# SparkFun_Micro_Bit_Moto_Bit.net
KiCad netlist of a schematic drawn in EAGLE
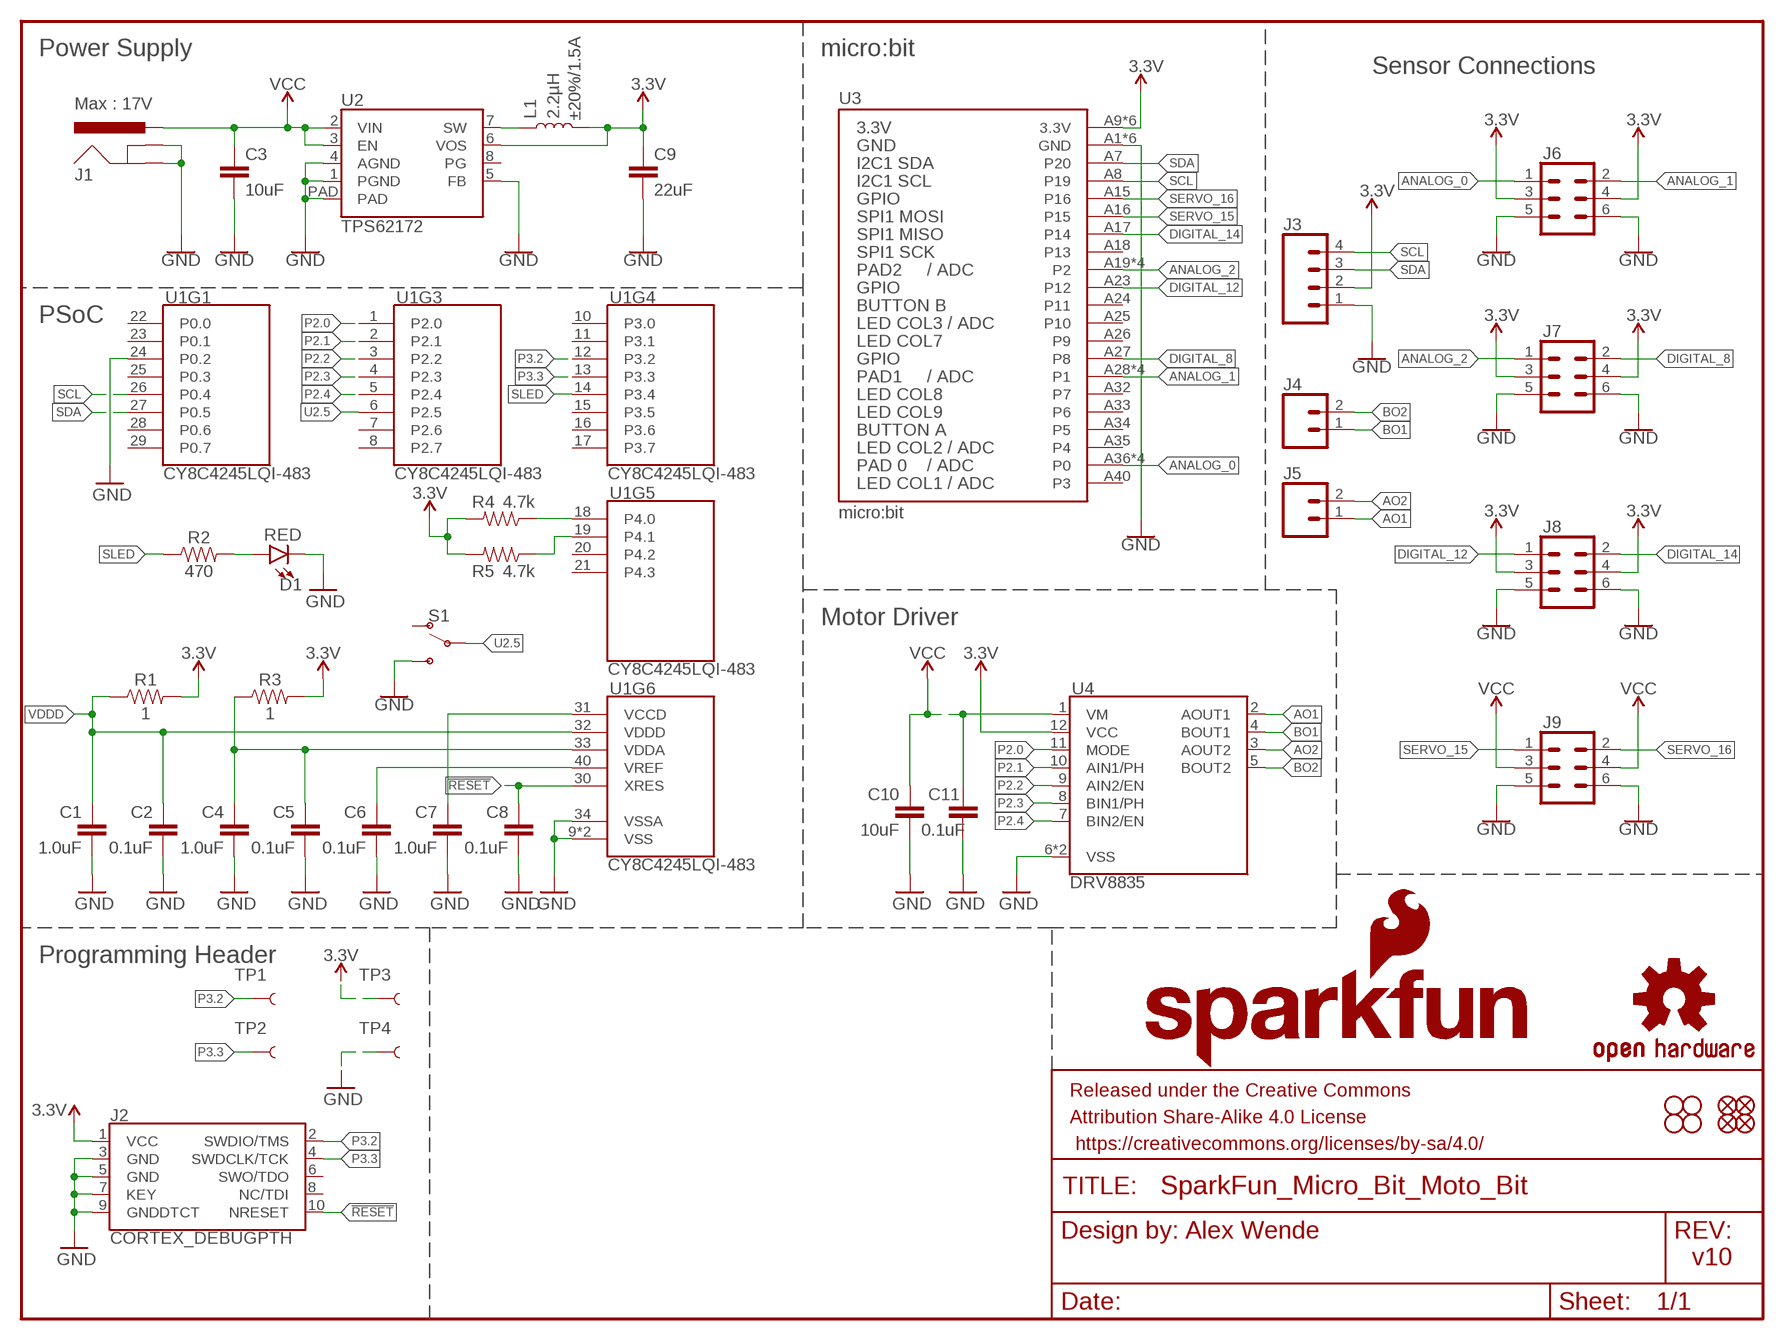
[diagram p0: schematic, sheet 1]

(export (version "E")
  (design (tool "Eeschema 10.0.6"))
  (components
    (comp (ref "C1")
      (value "1.0uF")
      (footprint "eagle-import:0603")
      (libsource (lib "eagle-import") (part "1.0UF-0603-16V-10%"))
    )
    (comp (ref "C2")
      (value "0.1uF")
      (footprint "eagle-import:0603")
      (libsource (lib "eagle-import") (part "0.1UF-0603-25V-(+80/-20%)"))
    )
    (comp (ref "C3")
      (value "10uF")
      (footprint "eagle-import:1210")
      (libsource (lib "eagle-import") (part "10UF-1210-50V-20%"))
    )
    (comp (ref "C4")
      (value "1.0uF")
      (footprint "eagle-import:0603")
      (libsource (lib "eagle-import") (part "1.0UF-0603-16V-10%"))
    )
    (comp (ref "C5")
      (value "0.1uF")
      (footprint "eagle-import:0603")
      (libsource (lib "eagle-import") (part "0.1UF-0603-25V-(+80/-20%)"))
    )
    (comp (ref "C6")
      (value "0.1uF")
      (footprint "eagle-import:0603")
      (libsource (lib "eagle-import") (part "0.1UF-0603-25V-(+80/-20%)"))
    )
    (comp (ref "C7")
      (value "1.0uF")
      (footprint "eagle-import:0603")
      (libsource (lib "eagle-import") (part "1.0UF-0603-16V-10%"))
    )
    (comp (ref "C8")
      (value "0.1uF")
      (footprint "eagle-import:0603")
      (libsource (lib "eagle-import") (part "0.1UF-0603-25V-(+80/-20%)"))
    )
    (comp (ref "C9")
      (value "22uF")
      (footprint "eagle-import:0805")
      (libsource (lib "eagle-import") (part "22UF-0805-6.3V-20%"))
    )
    (comp (ref "C10")
      (value "10uF")
      (footprint "eagle-import:1210")
      (libsource (lib "eagle-import") (part "10UF-1210-50V-20%"))
    )
    (comp (ref "C11")
      (value "0.1uF")
      (footprint "eagle-import:0603")
      (libsource (lib "eagle-import") (part "0.1UF-0603-25V-(+80/-20%)"))
    )
    (comp (ref "D1")
      (value "RED")
      (footprint "eagle-import:LED-0603")
      (libsource (lib "eagle-import") (part "LED-RED0603"))
    )
    (comp (ref "FD1")
      (value "FIDUCIALUFIDUCIAL")
      (footprint "eagle-import:FIDUCIAL-MICRO")
      (libsource (lib "eagle-import") (part "FIDUCIALUFIDUCIAL"))
    )
    (comp (ref "FD2")
      (value "FIDUCIALUFIDUCIAL")
      (footprint "eagle-import:FIDUCIAL-MICRO")
      (libsource (lib "eagle-import") (part "FIDUCIALUFIDUCIAL"))
    )
    (comp (ref "FD3")
      (value "FIDUCIALUFIDUCIAL")
      (footprint "eagle-import:FIDUCIAL-MICRO")
      (libsource (lib "eagle-import") (part "FIDUCIALUFIDUCIAL"))
    )
    (comp (ref "FD4")
      (value "FIDUCIALUFIDUCIAL")
      (footprint "eagle-import:FIDUCIAL-MICRO")
      (libsource (lib "eagle-import") (part "FIDUCIALUFIDUCIAL"))
    )
    (comp (ref "FRAME1")
      (value "FRAME-LETTER")
      (footprint "eagle-import:CREATIVE_COMMONS")
      (libsource (lib "eagle-import") (part "FRAME-LETTER"))
    )
    (comp (ref "H1")
      (value "STAND-OFF")
      (footprint "eagle-import:STAND-OFF")
      (libsource (lib "eagle-import") (part "STAND-OFF"))
    )
    (comp (ref "H2")
      (value "STAND-OFF")
      (footprint "eagle-import:STAND-OFF")
      (libsource (lib "eagle-import") (part "STAND-OFF"))
    )
    (comp (ref "H3")
      (value "STAND-OFF")
      (footprint "eagle-import:STAND-OFF")
      (libsource (lib "eagle-import") (part "STAND-OFF"))
    )
    (comp (ref "H4")
      (value "STAND-OFF")
      (footprint "eagle-import:STAND-OFF")
      (libsource (lib "eagle-import") (part "STAND-OFF"))
    )
    (comp (ref "J1")
      (value "POWER_JACKPTH_LOCK")
      (footprint "eagle-import:POWER_JACK_PTH_LOCK")
      (libsource (lib "eagle-import") (part "POWER_JACKPTH_LOCK"))
    )
    (comp (ref "J2")
      (value "CORTEX_DEBUGPTH")
      (footprint "eagle-import:2X5-PTH-1.27MM")
      (libsource (lib "eagle-import") (part "CORTEX_DEBUGPTH"))
    )
    (comp (ref "J3")
      (value "CONN_04SMD_STRAIGHT_COMBO")
      (footprint "eagle-import:1X04_SMD_VERTICAL_COMBO")
      (libsource (lib "eagle-import") (part "CONN_04SMD_STRAIGHT_COMBO"))
    )
    (comp (ref "J4")
      (value "CONN_02PTH_RA_FEMALE")
      (footprint "eagle-import:1X02_RA_FEMALE")
      (libsource (lib "eagle-import") (part "CONN_02PTH_RA_FEMALE"))
    )
    (comp (ref "J5")
      (value "CONN_02PTH_RA_FEMALE")
      (footprint "eagle-import:1X02_RA_FEMALE")
      (libsource (lib "eagle-import") (part "CONN_02PTH_RA_FEMALE"))
    )
    (comp (ref "J6")
      (value "CONN_03X2SMT")
      (footprint "eagle-import:2X3_SMT_POSTS")
      (libsource (lib "eagle-import") (part "CONN_03X2SMT"))
    )
    (comp (ref "J7")
      (value "CONN_03X2SMT")
      (footprint "eagle-import:2X3_SMT_POSTS")
      (libsource (lib "eagle-import") (part "CONN_03X2SMT"))
    )
    (comp (ref "J8")
      (value "CONN_03X2SMT")
      (footprint "eagle-import:2X3_SMT_POSTS")
      (libsource (lib "eagle-import") (part "CONN_03X2SMT"))
    )
    (comp (ref "J9")
      (value "CONN_03X2SMT")
      (footprint "eagle-import:2X3_SMT_POSTS")
      (libsource (lib "eagle-import") (part "CONN_03X2SMT"))
    )
    (comp (ref "L1")
      (value "2.2µH")
      (footprint "eagle-import:INDUCTOR_2.2UH")
      (libsource (lib "eagle-import") (part "INDUCTOR-VLF4012AT-2.2UH"))
    )
    (comp (ref "LOGO1")
      (value "SFE_LOGO_NAME_FLAME.3_INCH")
      (footprint "eagle-import:SFE_LOGO_NAME_FLAME_.3")
      (libsource (lib "eagle-import") (part "SFE_LOGO_NAME_FLAME.3_INCH"))
    )
    (comp (ref "LOGO2")
      (value "OSHW-LOGOL")
      (footprint "eagle-import:OSHW-LOGO-L")
      (libsource (lib "eagle-import") (part "OSHW-LOGOL"))
    )
    (comp (ref "R1")
      (value "1")
      (footprint "eagle-import:0603")
      (libsource (lib "eagle-import") (part "1OHM-0603-1/10W-1%"))
    )
    (comp (ref "R2")
      (value "470")
      (footprint "eagle-import:0603")
      (libsource (lib "eagle-import") (part "470OHM-0603-1/10W-1%"))
    )
    (comp (ref "R3")
      (value "1")
      (footprint "eagle-import:0603")
      (libsource (lib "eagle-import") (part "1OHM-0603-1/10W-1%"))
    )
    (comp (ref "R4")
      (value "4.7k")
      (footprint "eagle-import:0603")
      (libsource (lib "eagle-import") (part "4.7KOHM-0603-1/10W-1%"))
    )
    (comp (ref "R5")
      (value "4.7k")
      (footprint "eagle-import:0603")
      (libsource (lib "eagle-import") (part "4.7KOHM-0603-1/10W-1%"))
    )
    (comp (ref "S1")
      (value "SWITCH-SPDT-PTH-11.6X4.0MM")
      (footprint "eagle-import:SWITCH_SPDT_PTH_11.6X4.0MM")
      (libsource (lib "eagle-import") (part "SWITCH-SPDT-PTH-11.6X4.0MM"))
    )
    (comp (ref "TP1")
      (value "TEST-POINT3")
      (footprint "eagle-import:PAD.03X.03")
      (libsource (lib "eagle-import") (part "TEST-POINT3"))
    )
    (comp (ref "TP2")
      (value "TEST-POINT3")
      (footprint "eagle-import:PAD.03X.03")
      (libsource (lib "eagle-import") (part "TEST-POINT3"))
    )
    (comp (ref "TP3")
      (value "TEST-POINT3")
      (footprint "eagle-import:PAD.03X.03")
      (libsource (lib "eagle-import") (part "TEST-POINT3"))
    )
    (comp (ref "TP4")
      (value "TEST-POINT3")
      (footprint "eagle-import:PAD.03X.03")
      (libsource (lib "eagle-import") (part "TEST-POINT3"))
    )
    (comp (ref "U1")
      (value "CY8C4245LQI-483")
      (footprint "eagle-import:QFN-40")
      (libsource (lib "eagle-import") (part "PSOC4_4200_40QFN"))
    )
    (comp (ref "U2")
      (value "TPS62172")
      (footprint "eagle-import:WSON-8-PAD")
      (libsource (lib "eagle-import") (part "TPS62172"))
    )
    (comp (ref "U3")
      (value "micro:bit")
      (footprint "eagle-import:MICRO_BIT_RA_PTH")
      (libsource (lib "eagle-import") (part "MICRO{colon}BITLEDS_UP"))
    )
    (comp (ref "U4")
      (value "DRV8835")
      (footprint "eagle-import:WSON-12")
      (libsource (lib "eagle-import") (part "DRV883X"))
    )
  )
  (nets
    (net (code "1") (name "/~{RESET}") (class "Default")
      (node (ref "C8") (pin "1") (pinfunction "1_1") (pintype "passive"))
      (node (ref "J2") (pin "10") (pinfunction "NRESET_10") (pintype "bidirectional"))
      (node (ref "U1") (pin "30") (pinfunction "XRES_30") (pintype "bidirectional"))
    )
    (net (code "2") (name "3.3V") (class "Default")
      (node (ref "C9") (pin "1") (pinfunction "1_1") (pintype "passive"))
      (node (ref "J2") (pin "1") (pinfunction "VCC_1") (pintype "bidirectional"))
      (node (ref "J3") (pin "2") (pinfunction "2_2") (pintype "passive"))
      (node (ref "J6") (pin "3") (pinfunction "3_3") (pintype "bidirectional"))
      (node (ref "J6") (pin "4") (pinfunction "4_4") (pintype "bidirectional"))
      (node (ref "J7") (pin "3") (pinfunction "3_3") (pintype "bidirectional"))
      (node (ref "J7") (pin "4") (pinfunction "4_4") (pintype "bidirectional"))
      (node (ref "J8") (pin "3") (pinfunction "3_3") (pintype "bidirectional"))
      (node (ref "J8") (pin "4") (pinfunction "4_4") (pintype "bidirectional"))
      (node (ref "L1") (pin "P$2") (pinfunction "2_P$2") (pintype "passive"))
      (node (ref "R1") (pin "2") (pinfunction "2_2") (pintype "passive"))
      (node (ref "R3") (pin "2") (pinfunction "2_2") (pintype "passive"))
      (node (ref "R4") (pin "2") (pinfunction "2_2") (pintype "passive"))
      (node (ref "R5") (pin "2") (pinfunction "2_2") (pintype "passive"))
      (node (ref "TP3") (pin "P$1") (pinfunction "1_P$1") (pintype "bidirectional"))
      (node (ref "U2") (pin "6") (pinfunction "VOS_6") (pintype "bidirectional"))
      (node (ref "U3") (pin "A10") (pinfunction "3.3V_A10") (pintype "bidirectional"))
      (node (ref "U3") (pin "A11") (pinfunction "3.3V_A11") (pintype "bidirectional"))
      (node (ref "U3") (pin "A12") (pinfunction "3.3V_A12") (pintype "bidirectional"))
      (node (ref "U3") (pin "A13") (pinfunction "3.3V_A13") (pintype "bidirectional"))
      (node (ref "U3") (pin "A14") (pinfunction "3.3V_A14") (pintype "bidirectional"))
      (node (ref "U3") (pin "A9") (pinfunction "3.3V_A9") (pintype "bidirectional"))
      (node (ref "U4") (pin "12") (pinfunction "VCC_12") (pintype "bidirectional"))
    )
    (net (code "3") (name "ANALOG_0") (class "Default")
      (node (ref "J6") (pin "1") (pinfunction "1_1") (pintype "bidirectional"))
      (node (ref "U3") (pin "A36") (pinfunction "P0_A36") (pintype "bidirectional"))
      (node (ref "U3") (pin "A37") (pinfunction "P0_A37") (pintype "bidirectional"))
      (node (ref "U3") (pin "A38") (pinfunction "P0_A38") (pintype "bidirectional"))
      (node (ref "U3") (pin "A39") (pinfunction "P0_A39") (pintype "bidirectional"))
    )
    (net (code "4") (name "ANALOG_1") (class "Default")
      (node (ref "J6") (pin "2") (pinfunction "2_2") (pintype "bidirectional"))
      (node (ref "U3") (pin "A28") (pinfunction "P1_A28") (pintype "bidirectional"))
      (node (ref "U3") (pin "A29") (pinfunction "P1_A29") (pintype "bidirectional"))
      (node (ref "U3") (pin "A30") (pinfunction "P1_A30") (pintype "bidirectional"))
      (node (ref "U3") (pin "A31") (pinfunction "P1_A31") (pintype "bidirectional"))
    )
    (net (code "5") (name "ANALOG_2") (class "Default")
      (node (ref "J7") (pin "1") (pinfunction "1_1") (pintype "bidirectional"))
      (node (ref "U3") (pin "A19") (pinfunction "P2_A19") (pintype "bidirectional"))
      (node (ref "U3") (pin "A20") (pinfunction "P2_A20") (pintype "bidirectional"))
      (node (ref "U3") (pin "A21") (pinfunction "P2_A21") (pintype "bidirectional"))
      (node (ref "U3") (pin "A22") (pinfunction "P2_A22") (pintype "bidirectional"))
    )
    (net (code "6") (name "AO1") (class "Default")
      (node (ref "J5") (pin "1") (pinfunction "1_1") (pintype "passive"))
      (node (ref "U4") (pin "2") (pinfunction "AOUT1_2") (pintype "bidirectional"))
    )
    (net (code "7") (name "AO2") (class "Default")
      (node (ref "J5") (pin "2") (pinfunction "2_2") (pintype "passive"))
      (node (ref "U4") (pin "3") (pinfunction "AOUT2_3") (pintype "bidirectional"))
    )
    (net (code "8") (name "BO1") (class "Default")
      (node (ref "J4") (pin "1") (pinfunction "1_1") (pintype "passive"))
      (node (ref "U4") (pin "4") (pinfunction "BOUT1_4") (pintype "bidirectional"))
    )
    (net (code "9") (name "BO2") (class "Default")
      (node (ref "J4") (pin "2") (pinfunction "2_2") (pintype "passive"))
      (node (ref "U4") (pin "5") (pinfunction "BOUT2_5") (pintype "bidirectional"))
    )
    (net (code "10") (name "DIGITAL_8") (class "Default")
      (node (ref "J7") (pin "2") (pinfunction "2_2") (pintype "bidirectional"))
      (node (ref "U3") (pin "A27") (pinfunction "P8_A27") (pintype "bidirectional"))
    )
    (net (code "11") (name "DIGITAL_12") (class "Default")
      (node (ref "J8") (pin "1") (pinfunction "1_1") (pintype "bidirectional"))
      (node (ref "U3") (pin "A23") (pinfunction "P12_A23") (pintype "bidirectional"))
    )
    (net (code "12") (name "DIGITAL_14") (class "Default")
      (node (ref "J8") (pin "2") (pinfunction "2_2") (pintype "bidirectional"))
      (node (ref "U3") (pin "A17") (pinfunction "P14_A17") (pintype "bidirectional"))
    )
    (net (code "13") (name "GND") (class "Default")
      (node (ref "C1") (pin "2") (pinfunction "2_2") (pintype "passive"))
      (node (ref "C10") (pin "2") (pinfunction "2_2") (pintype "passive"))
      (node (ref "C11") (pin "2") (pinfunction "2_2") (pintype "passive"))
      (node (ref "C2") (pin "2") (pinfunction "2_2") (pintype "passive"))
      (node (ref "C3") (pin "2") (pinfunction "2_2") (pintype "passive"))
      (node (ref "C4") (pin "2") (pinfunction "2_2") (pintype "passive"))
      (node (ref "C5") (pin "2") (pinfunction "2_2") (pintype "passive"))
      (node (ref "C6") (pin "2") (pinfunction "2_2") (pintype "passive"))
      (node (ref "C7") (pin "2") (pinfunction "2_2") (pintype "passive"))
      (node (ref "C8") (pin "2") (pinfunction "2_2") (pintype "passive"))
      (node (ref "C9") (pin "2") (pinfunction "2_2") (pintype "passive"))
      (node (ref "D1") (pin "C") (pinfunction "C_C") (pintype "passive"))
      (node (ref "J1") (pin "GND") (pinfunction "GND_GND") (pintype "bidirectional"))
      (node (ref "J1") (pin "GNDBREAK") (pinfunction "GNDBREAK_GNDBREAK") (pintype "bidirectional"))
      (node (ref "J2") (pin "3") (pinfunction "GND_3") (pintype "bidirectional"))
      (node (ref "J2") (pin "5") (pinfunction "GND_5") (pintype "bidirectional"))
      (node (ref "J2") (pin "7") (pinfunction "KEY_7") (pintype "bidirectional"))
      (node (ref "J2") (pin "9") (pinfunction "GNDDTCT_9") (pintype "bidirectional"))
      (node (ref "J3") (pin "1") (pinfunction "1_1") (pintype "passive"))
      (node (ref "J6") (pin "5") (pinfunction "5_5") (pintype "bidirectional"))
      (node (ref "J6") (pin "6") (pinfunction "6_6") (pintype "bidirectional"))
      (node (ref "J7") (pin "5") (pinfunction "5_5") (pintype "bidirectional"))
      (node (ref "J7") (pin "6") (pinfunction "6_6") (pintype "bidirectional"))
      (node (ref "J8") (pin "5") (pinfunction "5_5") (pintype "bidirectional"))
      (node (ref "J8") (pin "6") (pinfunction "6_6") (pintype "bidirectional"))
      (node (ref "J9") (pin "5") (pinfunction "5_5") (pintype "bidirectional"))
      (node (ref "J9") (pin "6") (pinfunction "6_6") (pintype "bidirectional"))
      (node (ref "S1") (pin "3") (pinfunction "S_3") (pintype "passive"))
      (node (ref "TP4") (pin "P$1") (pinfunction "1_P$1") (pintype "bidirectional"))
      (node (ref "U1") (pin "24") (pinfunction "P0.2_24") (pintype "bidirectional"))
      (node (ref "U1") (pin "34") (pinfunction "VSSA_34") (pintype "bidirectional"))
      (node (ref "U1") (pin "9") (pinfunction "VSS_9") (pintype "bidirectional"))
      (node (ref "U1") (pin "EP") (pinfunction "VSS_EP") (pintype "bidirectional"))
      (node (ref "U2") (pin "1") (pinfunction "PGND_1") (pintype "bidirectional"))
      (node (ref "U2") (pin "4") (pinfunction "AGND_4") (pintype "bidirectional"))
      (node (ref "U2") (pin "5") (pinfunction "FB_5") (pintype "bidirectional"))
      (node (ref "U2") (pin "PAD") (pinfunction "PAD_PAD") (pintype "bidirectional"))
      (node (ref "U3") (pin "A1") (pinfunction "GND_A1") (pintype "bidirectional"))
      (node (ref "U3") (pin "A2") (pinfunction "GND_A2") (pintype "bidirectional"))
      (node (ref "U3") (pin "A3") (pinfunction "GND_A3") (pintype "bidirectional"))
      (node (ref "U3") (pin "A4") (pinfunction "GND_A4") (pintype "bidirectional"))
      (node (ref "U3") (pin "A5") (pinfunction "GND_A5") (pintype "bidirectional"))
      (node (ref "U3") (pin "A6") (pinfunction "GND_A6") (pintype "bidirectional"))
      (node (ref "U4") (pin "6") (pinfunction "VSS_6") (pintype "bidirectional"))
      (node (ref "U4") (pin "PAD") (pinfunction "VSS_PAD") (pintype "bidirectional"))
    )
    (net (code "14") (name "Net-(D1-PadA)") (class "Default")
      (node (ref "D1") (pin "A") (pinfunction "A_A") (pintype "passive"))
      (node (ref "R2") (pin "2") (pinfunction "2_2") (pintype "passive"))
    )
    (net (code "15") (name "Net-(L1-1)") (class "Default")
      (node (ref "L1") (pin "P$1") (pinfunction "1_P$1") (pintype "passive"))
      (node (ref "U2") (pin "7") (pinfunction "SW_7") (pintype "bidirectional"))
    )
    (net (code "16") (name "Net-(U1E-P4.0)") (class "Default")
      (node (ref "R4") (pin "1") (pinfunction "1_1") (pintype "passive"))
      (node (ref "U1") (pin "18") (pinfunction "P4.0_18") (pintype "bidirectional"))
    )
    (net (code "17") (name "Net-(U1E-P4.1)") (class "Default")
      (node (ref "R5") (pin "1") (pinfunction "1_1") (pintype "passive"))
      (node (ref "U1") (pin "19") (pinfunction "P4.1_19") (pintype "bidirectional"))
    )
    (net (code "18") (name "Net-(U1F-VCCD)") (class "Default")
      (node (ref "C7") (pin "1") (pinfunction "1_1") (pintype "passive"))
      (node (ref "U1") (pin "31") (pinfunction "VCCD_31") (pintype "bidirectional"))
    )
    (net (code "19") (name "Net-(U1F-VDDA)") (class "Default")
      (node (ref "C4") (pin "1") (pinfunction "1_1") (pintype "passive"))
      (node (ref "C5") (pin "1") (pinfunction "1_1") (pintype "passive"))
      (node (ref "R3") (pin "1") (pinfunction "1_1") (pintype "passive"))
      (node (ref "U1") (pin "33") (pinfunction "VDDA_33") (pintype "bidirectional"))
    )
    (net (code "20") (name "Net-(U1F-VREF)") (class "Default")
      (node (ref "C6") (pin "1") (pinfunction "1_1") (pintype "passive"))
      (node (ref "U1") (pin "40") (pinfunction "VREF_40") (pintype "bidirectional"))
    )
    (net (code "21") (name "P2.0") (class "Default")
      (node (ref "U1") (pin "1") (pinfunction "P2.0_1") (pintype "bidirectional"))
      (node (ref "U4") (pin "11") (pinfunction "MODE_11") (pintype "bidirectional"))
    )
    (net (code "22") (name "P2.1") (class "Default")
      (node (ref "U1") (pin "2") (pinfunction "P2.1_2") (pintype "bidirectional"))
      (node (ref "U4") (pin "10") (pinfunction "AIN1/PH_10") (pintype "bidirectional"))
    )
    (net (code "23") (name "P2.2") (class "Default")
      (node (ref "U1") (pin "3") (pinfunction "P2.2_3") (pintype "bidirectional"))
      (node (ref "U4") (pin "9") (pinfunction "AIN2/EN_9") (pintype "bidirectional"))
    )
    (net (code "24") (name "P2.3") (class "Default")
      (node (ref "U1") (pin "4") (pinfunction "P2.3_4") (pintype "bidirectional"))
      (node (ref "U4") (pin "8") (pinfunction "BIN1/PH_8") (pintype "bidirectional"))
    )
    (net (code "25") (name "P2.4") (class "Default")
      (node (ref "U1") (pin "5") (pinfunction "P2.4_5") (pintype "bidirectional"))
      (node (ref "U4") (pin "7") (pinfunction "BIN2/EN_7") (pintype "bidirectional"))
    )
    (net (code "26") (name "P3.2") (class "Default")
      (node (ref "J2") (pin "2") (pinfunction "SWDIO/TMS_2") (pintype "bidirectional"))
      (node (ref "TP1") (pin "P$1") (pinfunction "1_P$1") (pintype "bidirectional"))
      (node (ref "U1") (pin "12") (pinfunction "P3.2_12") (pintype "bidirectional"))
    )
    (net (code "27") (name "P3.3") (class "Default")
      (node (ref "J2") (pin "4") (pinfunction "SWDCLK/TCK_4") (pintype "bidirectional"))
      (node (ref "TP2") (pin "P$1") (pinfunction "1_P$1") (pintype "bidirectional"))
      (node (ref "U1") (pin "13") (pinfunction "P3.3_13") (pintype "bidirectional"))
    )
    (net (code "28") (name "SCL") (class "Default")
      (node (ref "J3") (pin "4") (pinfunction "4_4") (pintype "passive"))
      (node (ref "U1") (pin "26") (pinfunction "P0.4_26") (pintype "bidirectional"))
      (node (ref "U3") (pin "A8") (pinfunction "P19_A8") (pintype "bidirectional"))
    )
    (net (code "29") (name "SDA") (class "Default")
      (node (ref "J3") (pin "3") (pinfunction "3_3") (pintype "passive"))
      (node (ref "U1") (pin "27") (pinfunction "P0.5_27") (pintype "bidirectional"))
      (node (ref "U3") (pin "A7") (pinfunction "P20_A7") (pintype "bidirectional"))
    )
    (net (code "30") (name "SERVO_15") (class "Default")
      (node (ref "J9") (pin "1") (pinfunction "1_1") (pintype "bidirectional"))
      (node (ref "U3") (pin "A16") (pinfunction "P15_A16") (pintype "bidirectional"))
    )
    (net (code "31") (name "SERVO_16") (class "Default")
      (node (ref "J9") (pin "2") (pinfunction "2_2") (pintype "bidirectional"))
      (node (ref "U3") (pin "A15") (pinfunction "P16_A15") (pintype "bidirectional"))
    )
    (net (code "32") (name "SLED") (class "Default")
      (node (ref "R2") (pin "1") (pinfunction "1_1") (pintype "passive"))
      (node (ref "U1") (pin "14") (pinfunction "P3.4_14") (pintype "bidirectional"))
    )
    (net (code "33") (name "U2.5") (class "Default")
      (node (ref "S1") (pin "2") (pinfunction "P_2") (pintype "passive"))
      (node (ref "U1") (pin "6") (pinfunction "P2.5_6") (pintype "bidirectional"))
    )
    (net (code "34") (name "VCC") (class "Default")
      (node (ref "C10") (pin "1") (pinfunction "1_1") (pintype "passive"))
      (node (ref "C11") (pin "1") (pinfunction "1_1") (pintype "passive"))
      (node (ref "C3") (pin "1") (pinfunction "1_1") (pintype "passive"))
      (node (ref "J1") (pin "PWR") (pinfunction "PWR_PWR") (pintype "bidirectional"))
      (node (ref "J9") (pin "3") (pinfunction "3_3") (pintype "bidirectional"))
      (node (ref "J9") (pin "4") (pinfunction "4_4") (pintype "bidirectional"))
      (node (ref "U2") (pin "2") (pinfunction "VIN_2") (pintype "bidirectional"))
      (node (ref "U2") (pin "3") (pinfunction "EN_3") (pintype "bidirectional"))
      (node (ref "U4") (pin "1") (pinfunction "VM_1") (pintype "bidirectional"))
    )
    (net (code "35") (name "VDDD") (class "Default")
      (node (ref "C1") (pin "1") (pinfunction "1_1") (pintype "passive"))
      (node (ref "C2") (pin "1") (pinfunction "1_1") (pintype "passive"))
      (node (ref "R1") (pin "1") (pinfunction "1_1") (pintype "passive"))
      (node (ref "U1") (pin "32") (pinfunction "VDDD_32") (pintype "bidirectional"))
    )
    (net (code "36") (name "unconnected-(J2-NC{slash}TDI-Pad8)") (class "Default")
      (node (ref "J2") (pin "8") (pinfunction "NC/TDI_8") (pintype "bidirectional"))
    )
    (net (code "37") (name "unconnected-(J2-SWO{slash}TDO-Pad6)") (class "Default")
      (node (ref "J2") (pin "6") (pinfunction "SWO/TDO_6") (pintype "bidirectional"))
    )
    (net (code "38") (name "unconnected-(S1-O-Pad1)") (class "Default")
      (node (ref "S1") (pin "1") (pinfunction "O_1") (pintype "passive"))
    )
    (net (code "39") (name "unconnected-(U1A-P0.0-Pad22)") (class "Default")
      (node (ref "U1") (pin "22") (pinfunction "P0.0_22") (pintype "bidirectional"))
    )
    (net (code "40") (name "unconnected-(U1A-P0.1-Pad23)") (class "Default")
      (node (ref "U1") (pin "23") (pinfunction "P0.1_23") (pintype "bidirectional"))
    )
    (net (code "41") (name "unconnected-(U1A-P0.3-Pad25)") (class "Default")
      (node (ref "U1") (pin "25") (pinfunction "P0.3_25") (pintype "bidirectional"))
    )
    (net (code "42") (name "unconnected-(U1A-P0.6-Pad28)") (class "Default")
      (node (ref "U1") (pin "28") (pinfunction "P0.6_28") (pintype "bidirectional"))
    )
    (net (code "43") (name "unconnected-(U1A-P0.7-Pad29)") (class "Default")
      (node (ref "U1") (pin "29") (pinfunction "P0.7_29") (pintype "bidirectional"))
    )
    (net (code "44") (name "unconnected-(U1C-P2.6-Pad7)") (class "Default")
      (node (ref "U1") (pin "7") (pinfunction "P2.6_7") (pintype "bidirectional"))
    )
    (net (code "45") (name "unconnected-(U1C-P2.7-Pad8)") (class "Default")
      (node (ref "U1") (pin "8") (pinfunction "P2.7_8") (pintype "bidirectional"))
    )
    (net (code "46") (name "unconnected-(U1D-P3.0-Pad10)") (class "Default")
      (node (ref "U1") (pin "10") (pinfunction "P3.0_10") (pintype "bidirectional"))
    )
    (net (code "47") (name "unconnected-(U1D-P3.1-Pad11)") (class "Default")
      (node (ref "U1") (pin "11") (pinfunction "P3.1_11") (pintype "bidirectional"))
    )
    (net (code "48") (name "unconnected-(U1D-P3.5-Pad15)") (class "Default")
      (node (ref "U1") (pin "15") (pinfunction "P3.5_15") (pintype "bidirectional"))
    )
    (net (code "49") (name "unconnected-(U1D-P3.6-Pad16)") (class "Default")
      (node (ref "U1") (pin "16") (pinfunction "P3.6_16") (pintype "bidirectional"))
    )
    (net (code "50") (name "unconnected-(U1D-P3.7-Pad17)") (class "Default")
      (node (ref "U1") (pin "17") (pinfunction "P3.7_17") (pintype "bidirectional"))
    )
    (net (code "51") (name "unconnected-(U1E-P4.2-Pad20)") (class "Default")
      (node (ref "U1") (pin "20") (pinfunction "P4.2_20") (pintype "bidirectional"))
    )
    (net (code "52") (name "unconnected-(U1E-P4.3-Pad21)") (class "Default")
      (node (ref "U1") (pin "21") (pinfunction "P4.3_21") (pintype "bidirectional"))
    )
    (net (code "53") (name "unconnected-(U2-PG-Pad8)") (class "Default")
      (node (ref "U2") (pin "8") (pinfunction "PG_8") (pintype "bidirectional"))
    )
    (net (code "54") (name "unconnected-(U3-P3-PadA40)") (class "Default")
      (node (ref "U3") (pin "A40") (pinfunction "P3_A40") (pintype "bidirectional"))
    )
    (net (code "55") (name "unconnected-(U3-P4-PadA35)") (class "Default")
      (node (ref "U3") (pin "A35") (pinfunction "P4_A35") (pintype "bidirectional"))
    )
    (net (code "56") (name "unconnected-(U3-P5-PadA34)") (class "Default")
      (node (ref "U3") (pin "A34") (pinfunction "P5_A34") (pintype "bidirectional"))
    )
    (net (code "57") (name "unconnected-(U3-P6-PadA33)") (class "Default")
      (node (ref "U3") (pin "A33") (pinfunction "P6_A33") (pintype "bidirectional"))
    )
    (net (code "58") (name "unconnected-(U3-P7-PadA32)") (class "Default")
      (node (ref "U3") (pin "A32") (pinfunction "P7_A32") (pintype "bidirectional"))
    )
    (net (code "59") (name "unconnected-(U3-P9-PadA26)") (class "Default")
      (node (ref "U3") (pin "A26") (pinfunction "P9_A26") (pintype "bidirectional"))
    )
    (net (code "60") (name "unconnected-(U3-P10-PadA25)") (class "Default")
      (node (ref "U3") (pin "A25") (pinfunction "P10_A25") (pintype "bidirectional"))
    )
    (net (code "61") (name "unconnected-(U3-P11-PadA24)") (class "Default")
      (node (ref "U3") (pin "A24") (pinfunction "P11_A24") (pintype "bidirectional"))
    )
    (net (code "62") (name "unconnected-(U3-P13-PadA18)") (class "Default")
      (node (ref "U3") (pin "A18") (pinfunction "P13_A18") (pintype "bidirectional"))
    )
  )
)
